# SCH_286_BreakOut_Board_2023-05-22.net
KiCad netlist of a schematic drawn in EasyEDA
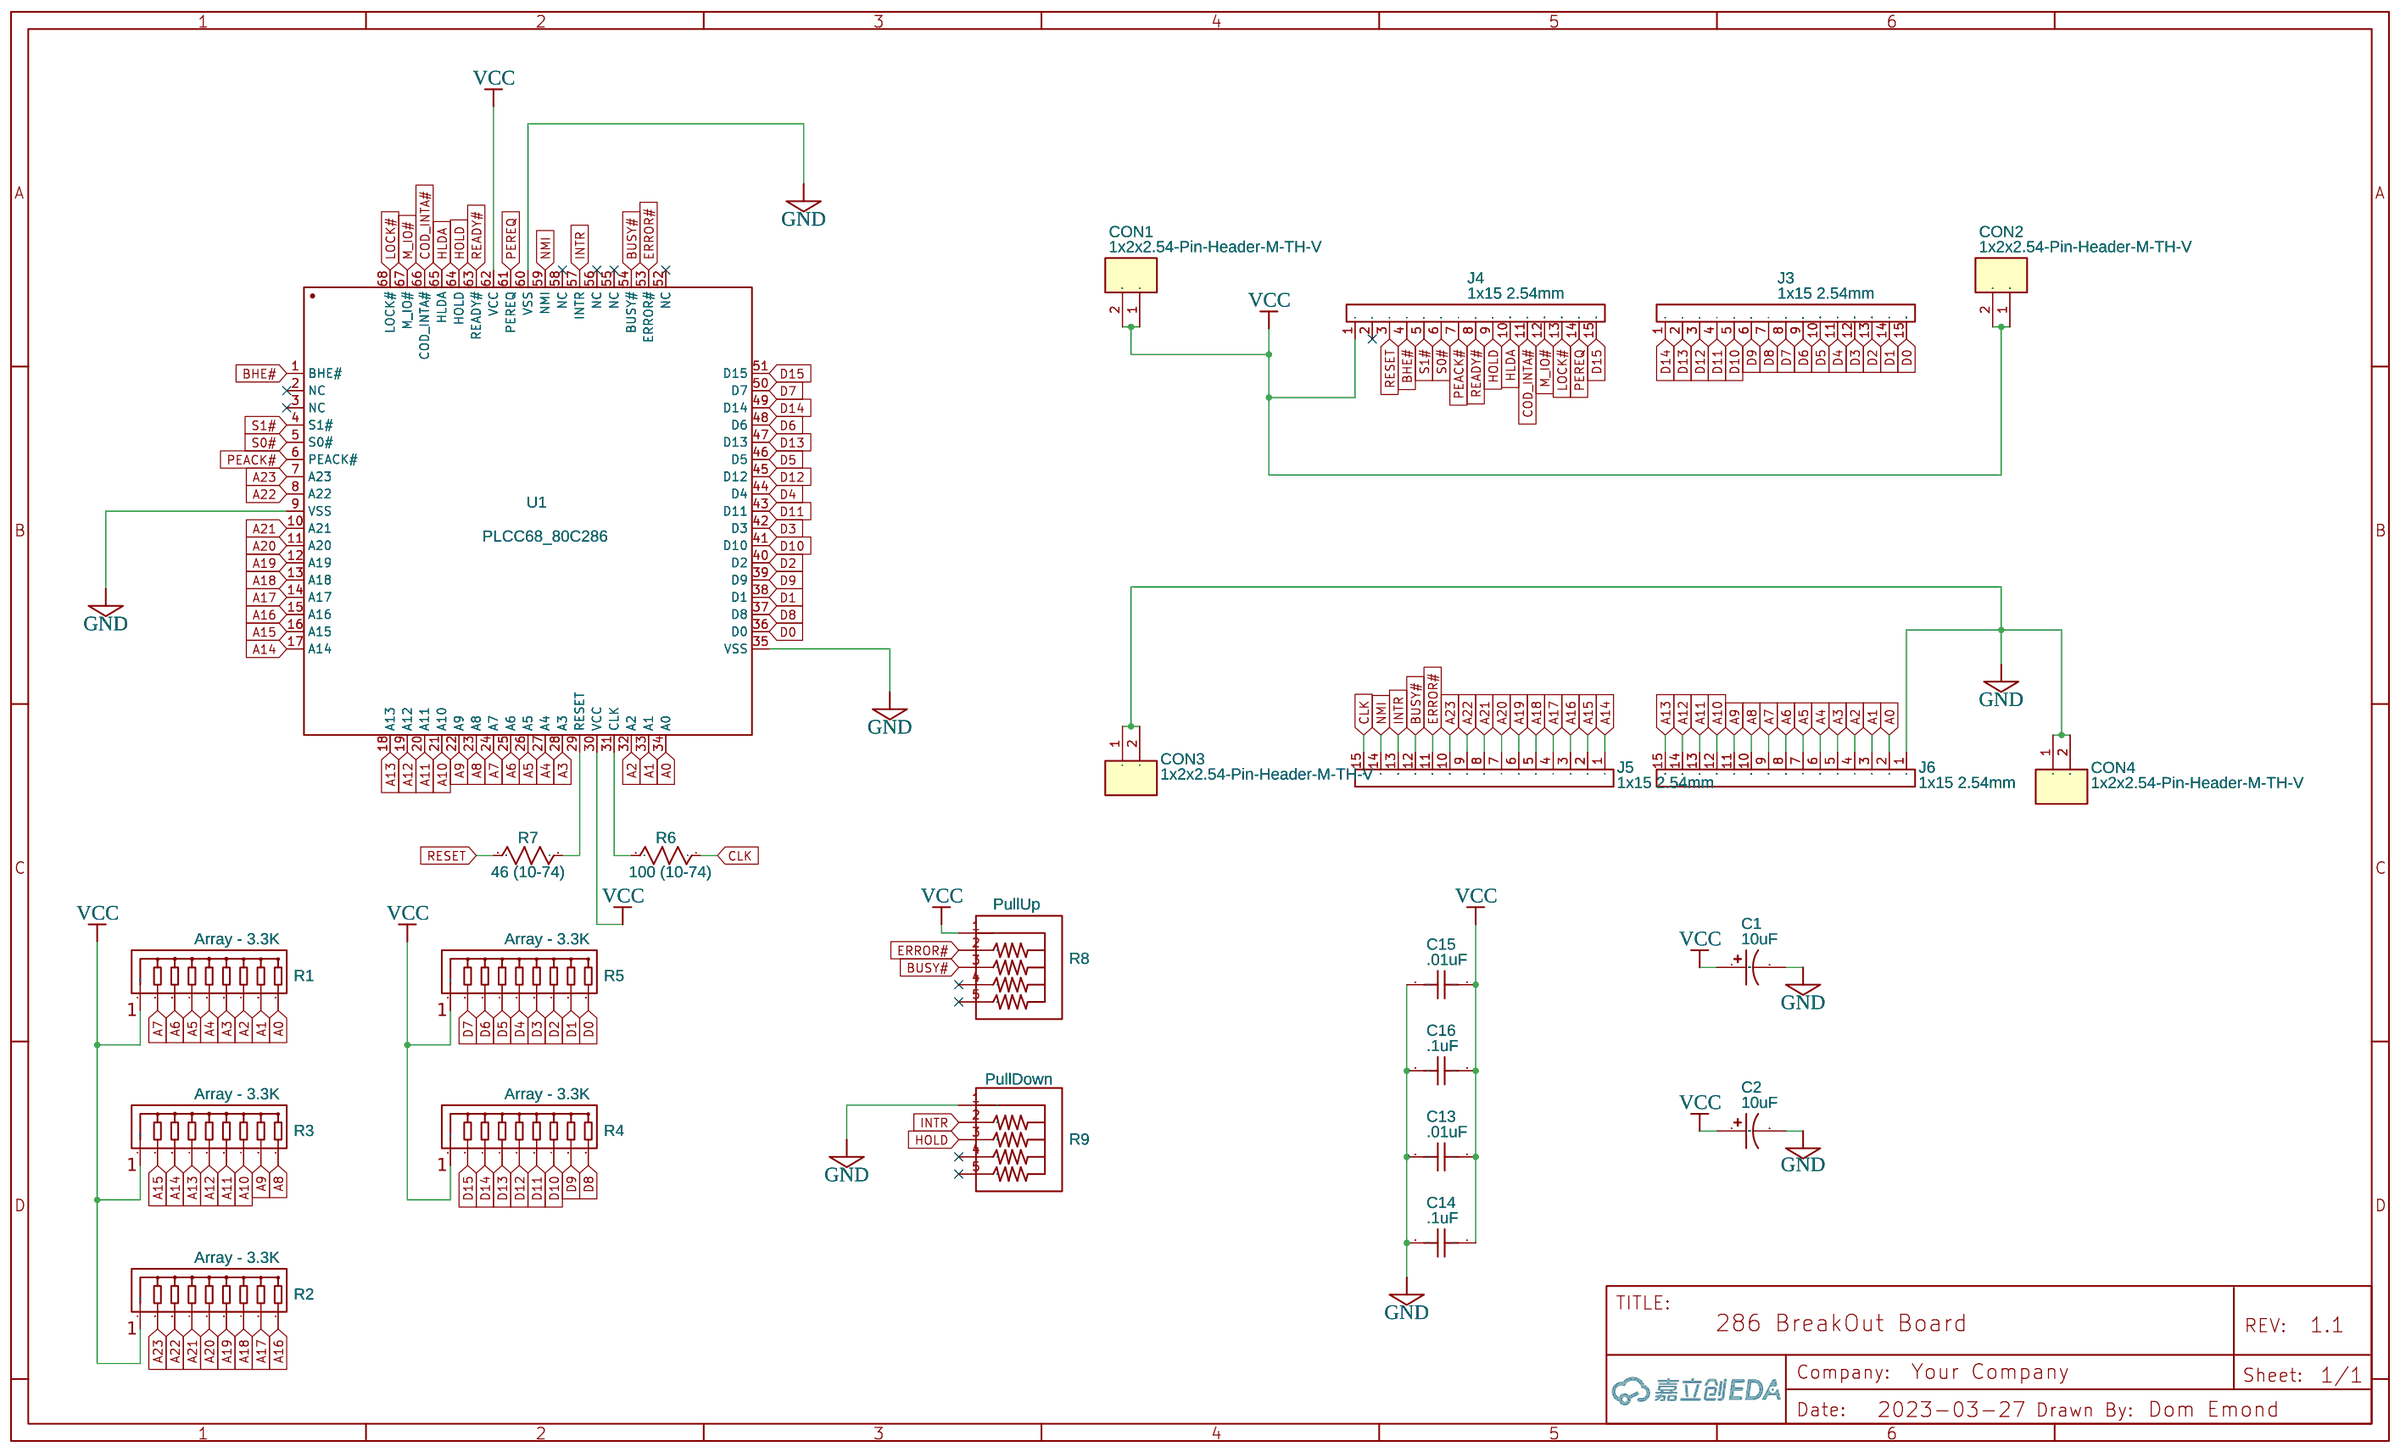
[diagram p0: schematic sheet]

(export (version "E")
  (design (tool "Eeschema 10.0.6"))
  (components
    (comp (ref "C1") (value "10uF") (libsource (lib "") (part "CE_TH_D6.3×F2.5_US")))
    (comp (ref "C2") (value "10uF") (libsource (lib "") (part "CE_TH_D6.3×F2.5_US_1")))
    (comp (ref "C13") (value ".01uF") (libsource (lib "") (part "C_RAD-0.1_US")))
    (comp (ref "C14") (value ".1uF") (libsource (lib "") (part "C_RAD-0.1_US")))
    (comp (ref "C15") (value ".01uF") (libsource (lib "") (part "C_RAD-0.1_US")))
    (comp (ref "C16") (value ".1uF") (libsource (lib "") (part "C_RAD-0.1_US")))
    (comp (ref "CON1")
      (value "1x2x2.54-Pin-Header-M-TH-V")
      (libsource (lib "") (part "1x2x2.54-Pin-Header-M-TH-V_1"))
    )
    (comp (ref "CON2")
      (value "1x2x2.54-Pin-Header-M-TH-V")
      (libsource (lib "") (part "1x2x2.54-Pin-Header-M-TH-V_1"))
    )
    (comp (ref "CON3")
      (value "1x2x2.54-Pin-Header-M-TH-V")
      (libsource (lib "") (part "1x2x2.54-Pin-Header-M-TH-V"))
    )
    (comp (ref "CON4")
      (value "1x2x2.54-Pin-Header-M-TH-V")
      (libsource (lib "") (part "1x2x2.54-Pin-Header-M-TH-V"))
    )
    (comp (ref "J3") (value "1x15 2.54mm") (libsource (lib "") (part "1x15 2.54mm_1")))
    (comp (ref "J4") (value "1x15 2.54mm") (libsource (lib "") (part "1x15 2.54mm_1")))
    (comp (ref "J5") (value "1x15 2.54mm") (libsource (lib "") (part "1x15 2.54mm")))
    (comp (ref "J6") (value "1x15 2.54mm") (libsource (lib "") (part "1x15 2.54mm")))
    (comp (ref "R1") (value "Array - 3.3K") (libsource (lib "") (part "RESISTOR-8XARRAY_SIP")))
    (comp (ref "R2") (value "Array - 3.3K") (libsource (lib "") (part "RESISTOR-8XARRAY_SIP")))
    (comp (ref "R3") (value "Array - 3.3K") (libsource (lib "") (part "RESISTOR-8XARRAY_SIP")))
    (comp (ref "R4") (value "Array - 3.3K") (libsource (lib "") (part "RESISTOR-8XARRAY_SIP_1")))
    (comp (ref "R5") (value "Array - 3.3K") (libsource (lib "") (part "RESISTOR-8XARRAY_SIP_1")))
    (comp (ref "R6") (value "100 (10-74)") (libsource (lib "") (part "RESISTOR-1/4W")))
    (comp (ref "R7") (value "46 (10-74)") (libsource (lib "") (part "RESISTOR-1/4W")))
    (comp (ref "R8")
      (value "PullUp")
      (fields
        (field (name "BOM_Manufacturer Part") "TT Electronics")
        (field (name "BOM_Supplier Part") "undefined")
      )
      (libsource (lib "") (part "4 Resistor Array"))
    )
    (comp (ref "R9")
      (value "PullDown")
      (fields
        (field (name "BOM_Manufacturer Part") "TT Electronics")
        (field (name "BOM_Supplier Part") "undefined")
      )
      (libsource (lib "") (part "4 Resistor Array"))
    )
    (comp (ref "U1")
      (value "PLCC68_80C286")
      (fields (field (name "BOM_Manufacturer Part") "PA68"))
      (libsource (lib "") (part "PLCC68_PA68"))
    )
  )
  (nets
    (net (code "1") (name "A0") (class "Default")
      (node (ref "J6") (pin "2") (pinfunction "2_2") (pintype "unspecified"))
      (node (ref "R1") (pin "9") (pintype "unspecified"))
      (node (ref "U1") (pin "34") (pinfunction "A0_34") (pintype "unspecified"))
    )
    (net (code "2") (name "A1") (class "Default")
      (node (ref "J6") (pin "3") (pinfunction "3_3") (pintype "unspecified"))
      (node (ref "R1") (pin "8") (pintype "unspecified"))
      (node (ref "U1") (pin "33") (pinfunction "A1_33") (pintype "unspecified"))
    )
    (net (code "3") (name "A2") (class "Default")
      (node (ref "J6") (pin "4") (pinfunction "4_4") (pintype "unspecified"))
      (node (ref "R1") (pin "7") (pintype "unspecified"))
      (node (ref "U1") (pin "32") (pinfunction "A2_32") (pintype "unspecified"))
    )
    (net (code "4") (name "A3") (class "Default")
      (node (ref "J6") (pin "5") (pinfunction "5_5") (pintype "unspecified"))
      (node (ref "R1") (pin "6") (pintype "unspecified"))
      (node (ref "U1") (pin "28") (pinfunction "A3_28") (pintype "unspecified"))
    )
    (net (code "5") (name "A4") (class "Default")
      (node (ref "J6") (pin "6") (pinfunction "6_6") (pintype "unspecified"))
      (node (ref "R1") (pin "5") (pintype "unspecified"))
      (node (ref "U1") (pin "27") (pinfunction "A4_27") (pintype "unspecified"))
    )
    (net (code "6") (name "A5") (class "Default")
      (node (ref "J6") (pin "7") (pinfunction "7_7") (pintype "unspecified"))
      (node (ref "R1") (pin "4") (pintype "unspecified"))
      (node (ref "U1") (pin "26") (pinfunction "A5_26") (pintype "unspecified"))
    )
    (net (code "7") (name "A6") (class "Default")
      (node (ref "J6") (pin "8") (pinfunction "8_8") (pintype "unspecified"))
      (node (ref "R1") (pin "3") (pintype "unspecified"))
      (node (ref "U1") (pin "25") (pinfunction "A6_25") (pintype "unspecified"))
    )
    (net (code "8") (name "A7") (class "Default")
      (node (ref "J6") (pin "9") (pinfunction "9_9") (pintype "unspecified"))
      (node (ref "R1") (pin "2") (pintype "unspecified"))
      (node (ref "U1") (pin "24") (pinfunction "A7_24") (pintype "unspecified"))
    )
    (net (code "9") (name "A8") (class "Default")
      (node (ref "J6") (pin "10") (pinfunction "10_10") (pintype "unspecified"))
      (node (ref "R3") (pin "9") (pintype "unspecified"))
      (node (ref "U1") (pin "23") (pinfunction "A8_23") (pintype "unspecified"))
    )
    (net (code "10") (name "A9") (class "Default")
      (node (ref "J6") (pin "11") (pinfunction "11_11") (pintype "unspecified"))
      (node (ref "R3") (pin "8") (pintype "unspecified"))
      (node (ref "U1") (pin "22") (pinfunction "A9_22") (pintype "unspecified"))
    )
    (net (code "11") (name "A10") (class "Default")
      (node (ref "J6") (pin "12") (pinfunction "12_12") (pintype "unspecified"))
      (node (ref "R3") (pin "7") (pintype "unspecified"))
      (node (ref "U1") (pin "21") (pinfunction "A10_21") (pintype "unspecified"))
    )
    (net (code "12") (name "A11") (class "Default")
      (node (ref "J6") (pin "13") (pinfunction "13_13") (pintype "unspecified"))
      (node (ref "R3") (pin "6") (pintype "unspecified"))
      (node (ref "U1") (pin "20") (pinfunction "A11_20") (pintype "unspecified"))
    )
    (net (code "13") (name "A12") (class "Default")
      (node (ref "J6") (pin "14") (pinfunction "14_14") (pintype "unspecified"))
      (node (ref "R3") (pin "5") (pintype "unspecified"))
      (node (ref "U1") (pin "19") (pinfunction "A12_19") (pintype "unspecified"))
    )
    (net (code "14") (name "A13") (class "Default")
      (node (ref "J6") (pin "15") (pinfunction "15_15") (pintype "unspecified"))
      (node (ref "R3") (pin "4") (pintype "unspecified"))
      (node (ref "U1") (pin "18") (pinfunction "A13_18") (pintype "unspecified"))
    )
    (net (code "15") (name "A14") (class "Default")
      (node (ref "J5") (pin "1") (pinfunction "1_1") (pintype "unspecified"))
      (node (ref "R3") (pin "3") (pintype "unspecified"))
      (node (ref "U1") (pin "17") (pinfunction "A14_17") (pintype "unspecified"))
    )
    (net (code "16") (name "A15") (class "Default")
      (node (ref "J5") (pin "2") (pinfunction "2_2") (pintype "unspecified"))
      (node (ref "R3") (pin "2") (pintype "unspecified"))
      (node (ref "U1") (pin "16") (pinfunction "A15_16") (pintype "unspecified"))
    )
    (net (code "17") (name "A16") (class "Default")
      (node (ref "J5") (pin "3") (pinfunction "3_3") (pintype "unspecified"))
      (node (ref "R2") (pin "9") (pintype "unspecified"))
      (node (ref "U1") (pin "15") (pinfunction "A16_15") (pintype "unspecified"))
    )
    (net (code "18") (name "A17") (class "Default")
      (node (ref "J5") (pin "4") (pinfunction "4_4") (pintype "unspecified"))
      (node (ref "R2") (pin "8") (pintype "unspecified"))
      (node (ref "U1") (pin "14") (pinfunction "A17_14") (pintype "unspecified"))
    )
    (net (code "19") (name "A18") (class "Default")
      (node (ref "J5") (pin "5") (pinfunction "5_5") (pintype "unspecified"))
      (node (ref "R2") (pin "7") (pintype "unspecified"))
      (node (ref "U1") (pin "13") (pinfunction "A18_13") (pintype "unspecified"))
    )
    (net (code "20") (name "A19") (class "Default")
      (node (ref "J5") (pin "6") (pinfunction "6_6") (pintype "unspecified"))
      (node (ref "R2") (pin "6") (pintype "unspecified"))
      (node (ref "U1") (pin "12") (pinfunction "A19_12") (pintype "unspecified"))
    )
    (net (code "21") (name "A20") (class "Default")
      (node (ref "J5") (pin "7") (pinfunction "7_7") (pintype "unspecified"))
      (node (ref "R2") (pin "5") (pintype "unspecified"))
      (node (ref "U1") (pin "11") (pinfunction "A20_11") (pintype "unspecified"))
    )
    (net (code "22") (name "A21") (class "Default")
      (node (ref "J5") (pin "8") (pinfunction "8_8") (pintype "unspecified"))
      (node (ref "R2") (pin "4") (pintype "unspecified"))
      (node (ref "U1") (pin "10") (pinfunction "A21_10") (pintype "unspecified"))
    )
    (net (code "23") (name "A22") (class "Default")
      (node (ref "J5") (pin "9") (pinfunction "9_9") (pintype "unspecified"))
      (node (ref "R2") (pin "3") (pintype "unspecified"))
      (node (ref "U1") (pin "8") (pinfunction "A22_8") (pintype "unspecified"))
    )
    (net (code "24") (name "A23") (class "Default")
      (node (ref "J5") (pin "10") (pinfunction "10_10") (pintype "unspecified"))
      (node (ref "R2") (pin "2") (pintype "unspecified"))
      (node (ref "U1") (pin "7") (pinfunction "A23_7") (pintype "unspecified"))
    )
    (net (code "25") (name "BHE#") (class "Default")
      (node (ref "J4") (pin "4") (pinfunction "4_4") (pintype "unspecified"))
      (node (ref "U1") (pin "1") (pinfunction "BHE#_1") (pintype "unspecified"))
    )
    (net (code "26") (name "BUSY#") (class "Default")
      (node (ref "J5") (pin "12") (pinfunction "12_12") (pintype "unspecified"))
      (node (ref "R8") (pin "3") (pinfunction "3_3") (pintype "unspecified"))
      (node (ref "U1") (pin "54") (pinfunction "BUSY#_54") (pintype "unspecified"))
    )
    (net (code "27") (name "CLK") (class "Default")
      (node (ref "J5") (pin "15") (pinfunction "15_15") (pintype "unspecified"))
      (node (ref "R6") (pin "1") (pinfunction "1_1") (pintype "unspecified"))
    )
    (net (code "28") (name "COD_INTA#") (class "Default")
      (node (ref "J4") (pin "11") (pinfunction "11_11") (pintype "unspecified"))
      (node (ref "U1") (pin "66") (pinfunction "COD_INTA#_66") (pintype "unspecified"))
    )
    (net (code "29") (name "D0") (class "Default")
      (node (ref "J3") (pin "15") (pinfunction "15_15") (pintype "unspecified"))
      (node (ref "R5") (pin "9") (pintype "unspecified"))
      (node (ref "U1") (pin "36") (pinfunction "D0_36") (pintype "unspecified"))
    )
    (net (code "30") (name "D1") (class "Default")
      (node (ref "J3") (pin "14") (pinfunction "14_14") (pintype "unspecified"))
      (node (ref "R5") (pin "8") (pintype "unspecified"))
      (node (ref "U1") (pin "38") (pinfunction "D1_38") (pintype "unspecified"))
    )
    (net (code "31") (name "D2") (class "Default")
      (node (ref "J3") (pin "13") (pinfunction "13_13") (pintype "unspecified"))
      (node (ref "R5") (pin "7") (pintype "unspecified"))
      (node (ref "U1") (pin "40") (pinfunction "D2_40") (pintype "unspecified"))
    )
    (net (code "32") (name "D3") (class "Default")
      (node (ref "J3") (pin "12") (pinfunction "12_12") (pintype "unspecified"))
      (node (ref "R5") (pin "6") (pintype "unspecified"))
      (node (ref "U1") (pin "42") (pinfunction "D3_42") (pintype "unspecified"))
    )
    (net (code "33") (name "D4") (class "Default")
      (node (ref "J3") (pin "11") (pinfunction "11_11") (pintype "unspecified"))
      (node (ref "R5") (pin "5") (pintype "unspecified"))
      (node (ref "U1") (pin "44") (pinfunction "D4_44") (pintype "unspecified"))
    )
    (net (code "34") (name "D5") (class "Default")
      (node (ref "J3") (pin "10") (pinfunction "10_10") (pintype "unspecified"))
      (node (ref "R5") (pin "4") (pintype "unspecified"))
      (node (ref "U1") (pin "46") (pinfunction "D5_46") (pintype "unspecified"))
    )
    (net (code "35") (name "D6") (class "Default")
      (node (ref "J3") (pin "9") (pinfunction "9_9") (pintype "unspecified"))
      (node (ref "R5") (pin "3") (pintype "unspecified"))
      (node (ref "U1") (pin "48") (pinfunction "D6_48") (pintype "unspecified"))
    )
    (net (code "36") (name "D7") (class "Default")
      (node (ref "J3") (pin "8") (pinfunction "8_8") (pintype "unspecified"))
      (node (ref "R5") (pin "2") (pintype "unspecified"))
      (node (ref "U1") (pin "50") (pinfunction "D7_50") (pintype "unspecified"))
    )
    (net (code "37") (name "D8") (class "Default")
      (node (ref "J3") (pin "7") (pinfunction "7_7") (pintype "unspecified"))
      (node (ref "R4") (pin "9") (pintype "unspecified"))
      (node (ref "U1") (pin "37") (pinfunction "D8_37") (pintype "unspecified"))
    )
    (net (code "38") (name "D9") (class "Default")
      (node (ref "J3") (pin "6") (pinfunction "6_6") (pintype "unspecified"))
      (node (ref "R4") (pin "8") (pintype "unspecified"))
      (node (ref "U1") (pin "39") (pinfunction "D9_39") (pintype "unspecified"))
    )
    (net (code "39") (name "D10") (class "Default")
      (node (ref "J3") (pin "5") (pinfunction "5_5") (pintype "unspecified"))
      (node (ref "R4") (pin "7") (pintype "unspecified"))
      (node (ref "U1") (pin "41") (pinfunction "D10_41") (pintype "unspecified"))
    )
    (net (code "40") (name "D11") (class "Default")
      (node (ref "J3") (pin "4") (pinfunction "4_4") (pintype "unspecified"))
      (node (ref "R4") (pin "6") (pintype "unspecified"))
      (node (ref "U1") (pin "43") (pinfunction "D11_43") (pintype "unspecified"))
    )
    (net (code "41") (name "D12") (class "Default")
      (node (ref "J3") (pin "3") (pinfunction "3_3") (pintype "unspecified"))
      (node (ref "R4") (pin "5") (pintype "unspecified"))
      (node (ref "U1") (pin "45") (pinfunction "D12_45") (pintype "unspecified"))
    )
    (net (code "42") (name "D13") (class "Default")
      (node (ref "J3") (pin "2") (pinfunction "2_2") (pintype "unspecified"))
      (node (ref "R4") (pin "4") (pintype "unspecified"))
      (node (ref "U1") (pin "47") (pinfunction "D13_47") (pintype "unspecified"))
    )
    (net (code "43") (name "D14") (class "Default")
      (node (ref "J3") (pin "1") (pinfunction "1_1") (pintype "unspecified"))
      (node (ref "R4") (pin "3") (pintype "unspecified"))
      (node (ref "U1") (pin "49") (pinfunction "D14_49") (pintype "unspecified"))
    )
    (net (code "44") (name "D15") (class "Default")
      (node (ref "J4") (pin "15") (pinfunction "15_15") (pintype "unspecified"))
      (node (ref "R4") (pin "2") (pintype "unspecified"))
      (node (ref "U1") (pin "51") (pinfunction "D15_51") (pintype "unspecified"))
    )
    (net (code "45") (name "ERROR#") (class "Default")
      (node (ref "J5") (pin "11") (pinfunction "11_11") (pintype "unspecified"))
      (node (ref "R8") (pin "2") (pinfunction "2_2") (pintype "unspecified"))
      (node (ref "U1") (pin "53") (pinfunction "ERROR#_53") (pintype "unspecified"))
    )
    (net (code "46") (name "GND") (class "Default")
      (node (ref "C1") (pin "2") (pinfunction "2_2") (pintype "unspecified"))
      (node (ref "C13") (pin "2") (pinfunction "2_2") (pintype "unspecified"))
      (node (ref "C14") (pin "2") (pinfunction "2_2") (pintype "unspecified"))
      (node (ref "C15") (pin "2") (pinfunction "2_2") (pintype "unspecified"))
      (node (ref "C16") (pin "2") (pinfunction "2_2") (pintype "unspecified"))
      (node (ref "C2") (pin "2") (pinfunction "2_2") (pintype "unspecified"))
      (node (ref "CON3") (pin "1") (pinfunction "1_1") (pintype "unspecified"))
      (node (ref "CON3") (pin "2") (pinfunction "2_2") (pintype "unspecified"))
      (node (ref "CON4") (pin "1") (pinfunction "1_1") (pintype "unspecified"))
      (node (ref "CON4") (pin "2") (pinfunction "2_2") (pintype "unspecified"))
      (node (ref "J6") (pin "1") (pinfunction "1_1") (pintype "unspecified"))
      (node (ref "R9") (pin "1") (pinfunction "1_1") (pintype "unspecified"))
      (node (ref "U1") (pin "35") (pinfunction "VSS_35") (pintype "unspecified"))
      (node (ref "U1") (pin "60") (pinfunction "VSS_60") (pintype "unspecified"))
      (node (ref "U1") (pin "9") (pinfunction "VSS_9") (pintype "unspecified"))
    )
    (net (code "47") (name "HLDA") (class "Default")
      (node (ref "J4") (pin "10") (pinfunction "10_10") (pintype "unspecified"))
      (node (ref "U1") (pin "65") (pinfunction "HLDA_65") (pintype "unspecified"))
    )
    (net (code "48") (name "HOLD") (class "Default")
      (node (ref "J4") (pin "9") (pinfunction "9_9") (pintype "unspecified"))
      (node (ref "R9") (pin "3") (pinfunction "3_3") (pintype "unspecified"))
      (node (ref "U1") (pin "64") (pinfunction "HOLD_64") (pintype "unspecified"))
    )
    (net (code "49") (name "INTR") (class "Default")
      (node (ref "J5") (pin "13") (pinfunction "13_13") (pintype "unspecified"))
      (node (ref "R9") (pin "2") (pinfunction "2_2") (pintype "unspecified"))
      (node (ref "U1") (pin "57") (pinfunction "INTR_57") (pintype "unspecified"))
    )
    (net (code "50") (name "LOCK#") (class "Default")
      (node (ref "J4") (pin "13") (pinfunction "13_13") (pintype "unspecified"))
      (node (ref "U1") (pin "68") (pinfunction "LOCK#_68") (pintype "unspecified"))
    )
    (net (code "51") (name "M_IO#") (class "Default")
      (node (ref "J4") (pin "12") (pinfunction "12_12") (pintype "unspecified"))
      (node (ref "U1") (pin "67") (pinfunction "M_IO#_67") (pintype "unspecified"))
    )
    (net (code "52") (name "NMI") (class "Default")
      (node (ref "J5") (pin "14") (pinfunction "14_14") (pintype "unspecified"))
      (node (ref "U1") (pin "59") (pinfunction "NMI_59") (pintype "unspecified"))
    )
    (net (code "53") (name "Net-(U1-CLK)") (class "Default")
      (node (ref "R6") (pin "2") (pinfunction "2_2") (pintype "unspecified"))
      (node (ref "U1") (pin "31") (pinfunction "CLK_31") (pintype "unspecified"))
    )
    (net (code "54") (name "Net-(U1-RESET)") (class "Default")
      (node (ref "R7") (pin "1") (pinfunction "1_1") (pintype "unspecified"))
      (node (ref "U1") (pin "29") (pinfunction "RESET_29") (pintype "unspecified"))
    )
    (net (code "55") (name "PEACK#") (class "Default")
      (node (ref "J4") (pin "7") (pinfunction "7_7") (pintype "unspecified"))
      (node (ref "U1") (pin "6") (pinfunction "PEACK#_6") (pintype "unspecified"))
    )
    (net (code "56") (name "PEREQ") (class "Default")
      (node (ref "J4") (pin "14") (pinfunction "14_14") (pintype "unspecified"))
      (node (ref "U1") (pin "61") (pinfunction "PEREQ_61") (pintype "unspecified"))
    )
    (net (code "57") (name "READY#") (class "Default")
      (node (ref "J4") (pin "8") (pinfunction "8_8") (pintype "unspecified"))
      (node (ref "U1") (pin "63") (pinfunction "READY#_63") (pintype "unspecified"))
    )
    (net (code "58") (name "RESET") (class "Default")
      (node (ref "J4") (pin "3") (pinfunction "3_3") (pintype "unspecified"))
      (node (ref "R7") (pin "2") (pinfunction "2_2") (pintype "unspecified"))
    )
    (net (code "59") (name "S0#") (class "Default")
      (node (ref "J4") (pin "6") (pinfunction "6_6") (pintype "unspecified"))
      (node (ref "U1") (pin "5") (pinfunction "S0#_5") (pintype "unspecified"))
    )
    (net (code "60") (name "S1#") (class "Default")
      (node (ref "J4") (pin "5") (pinfunction "5_5") (pintype "unspecified"))
      (node (ref "U1") (pin "4") (pinfunction "S1#_4") (pintype "unspecified"))
    )
    (net (code "61") (name "VCC") (class "Default")
      (node (ref "C1") (pin "1") (pinfunction "1_1") (pintype "unspecified"))
      (node (ref "C13") (pin "1") (pinfunction "1_1") (pintype "unspecified"))
      (node (ref "C14") (pin "1") (pinfunction "1_1") (pintype "unspecified"))
      (node (ref "C15") (pin "1") (pinfunction "1_1") (pintype "unspecified"))
      (node (ref "C16") (pin "1") (pinfunction "1_1") (pintype "unspecified"))
      (node (ref "C2") (pin "1") (pinfunction "1_1") (pintype "unspecified"))
      (node (ref "CON1") (pin "1") (pinfunction "1_1") (pintype "unspecified"))
      (node (ref "CON1") (pin "2") (pinfunction "2_2") (pintype "unspecified"))
      (node (ref "CON2") (pin "1") (pinfunction "1_1") (pintype "unspecified"))
      (node (ref "CON2") (pin "2") (pinfunction "2_2") (pintype "unspecified"))
      (node (ref "J4") (pin "1") (pinfunction "1_1") (pintype "unspecified"))
      (node (ref "R1") (pin "1") (pinfunction "Com_1") (pintype "unspecified"))
      (node (ref "R2") (pin "1") (pinfunction "Com_1") (pintype "unspecified"))
      (node (ref "R3") (pin "1") (pinfunction "Com_1") (pintype "unspecified"))
      (node (ref "R4") (pin "1") (pinfunction "Com_1") (pintype "unspecified"))
      (node (ref "R5") (pin "1") (pinfunction "Com_1") (pintype "unspecified"))
      (node (ref "R8") (pin "1") (pinfunction "1_1") (pintype "unspecified"))
      (node (ref "U1") (pin "30") (pinfunction "VCC_30") (pintype "unspecified"))
      (node (ref "U1") (pin "62") (pinfunction "VCC_62") (pintype "unspecified"))
    )
    (net (code "62") (name "unconnected-(J4-Pad2)") (class "Default")
      (node (ref "J4") (pin "2") (pinfunction "2_2") (pintype "unspecified+no_connect"))
    )
    (net (code "63") (name "unconnected-(R8-Pad4)") (class "Default")
      (node (ref "R8") (pin "4") (pinfunction "4_4") (pintype "unspecified+no_connect"))
    )
    (net (code "64") (name "unconnected-(R8-Pad5)") (class "Default")
      (node (ref "R8") (pin "5") (pinfunction "5_5") (pintype "unspecified+no_connect"))
    )
    (net (code "65") (name "unconnected-(R9-Pad4)") (class "Default")
      (node (ref "R9") (pin "4") (pinfunction "4_4") (pintype "unspecified+no_connect"))
    )
    (net (code "66") (name "unconnected-(R9-Pad5)") (class "Default")
      (node (ref "R9") (pin "5") (pinfunction "5_5") (pintype "unspecified+no_connect"))
    )
    (net (code "67") (name "unconnected-(U1-NC-Pad2)") (class "Default")
      (node (ref "U1") (pin "2") (pinfunction "NC_2") (pintype "unspecified+no_connect"))
    )
    (net (code "68") (name "unconnected-(U1-NC-Pad3)") (class "Default")
      (node (ref "U1") (pin "3") (pinfunction "NC_3") (pintype "unspecified+no_connect"))
    )
    (net (code "69") (name "unconnected-(U1-NC-Pad52)") (class "Default")
      (node (ref "U1") (pin "52") (pinfunction "NC_52") (pintype "unspecified+no_connect"))
    )
    (net (code "70") (name "unconnected-(U1-NC-Pad55)") (class "Default")
      (node (ref "U1") (pin "55") (pinfunction "NC_55") (pintype "unspecified+no_connect"))
    )
    (net (code "71") (name "unconnected-(U1-NC-Pad56)") (class "Default")
      (node (ref "U1") (pin "56") (pinfunction "NC_56") (pintype "unspecified+no_connect"))
    )
    (net (code "72") (name "unconnected-(U1-NC-Pad58)") (class "Default")
      (node (ref "U1") (pin "58") (pinfunction "NC_58") (pintype "unspecified+no_connect"))
    )
  )
)
